# motherboard_zaloha_s_medi.net
KiCad netlist of a schematic drawn in EAGLE
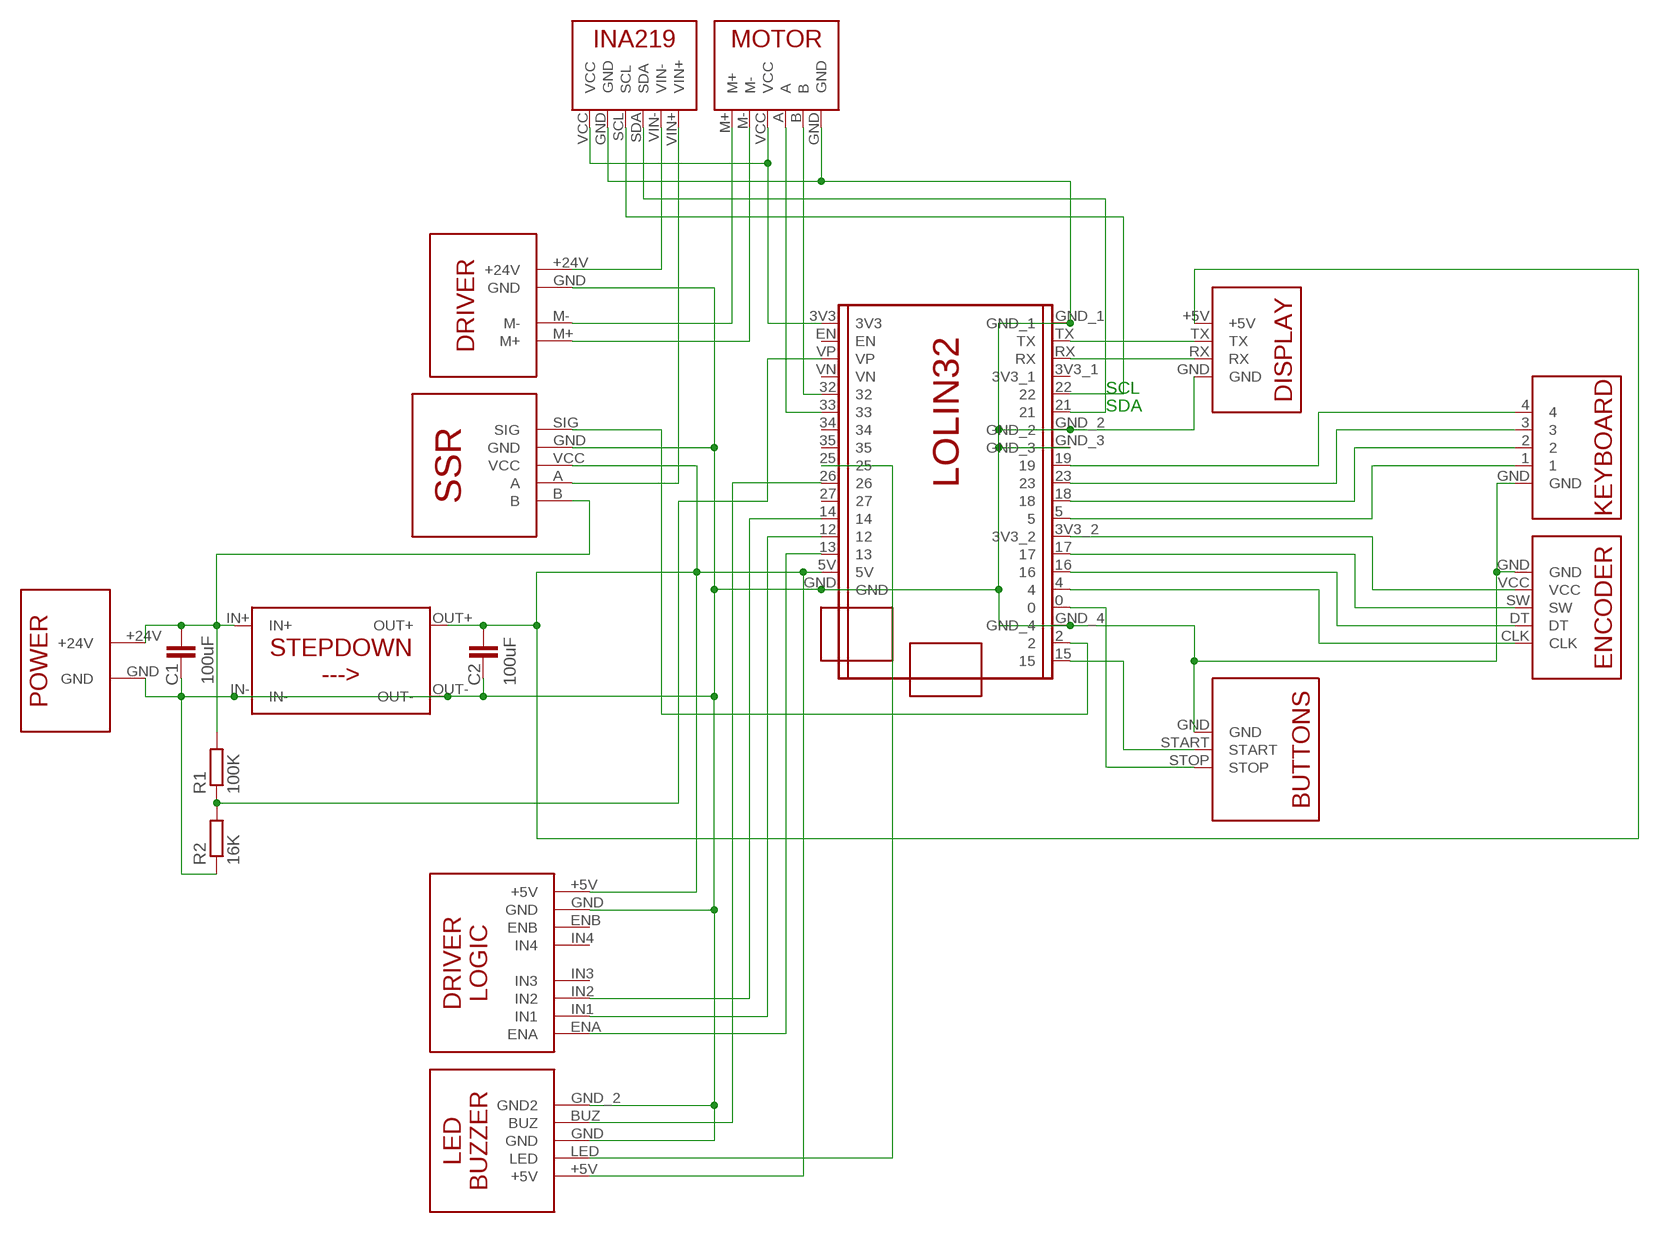
[diagram p0: schematic, sheet 1]

(export (version "E")
  (design (tool "Eeschema 10.0.6"))
  (components
    (comp (ref "C1")
      (value "100uF")
      (footprint "eagle-import:C5B2.5")
      (libsource (lib "eagle-import") (part "C5/2.5"))
    )
    (comp (ref "C2")
      (value "100uF")
      (footprint "eagle-import:C5B2.5")
      (libsource (lib "eagle-import") (part "C5/2.5"))
    )
    (comp (ref "R1")
      (value "100K")
      (footprint "eagle-import:0207_7")
      (libsource (lib "eagle-import") (part "R-EU_0207/7"))
    )
    (comp (ref "R2")
      (value "16K")
      (footprint "eagle-import:0207_7")
      (libsource (lib "eagle-import") (part "R-EU_0207/7"))
    )
    (comp (ref "U$1")
      (value "B_DISPLAY")
      (footprint "eagle-import:B_DISPLAY")
      (libsource (lib "eagle-import") (part "B_DISPLAY"))
    )
    (comp (ref "U$2")
      (value "INA219")
      (footprint "eagle-import:INA219")
      (libsource (lib "eagle-import") (part "INA219"))
    )
    (comp (ref "U$3")
      (value "B_MOTOR")
      (footprint "eagle-import:B_MOTOR")
      (libsource (lib "eagle-import") (part "B_MOTOR"))
    )
    (comp (ref "U$4")
      (value "B_KLAVESNICE")
      (footprint "eagle-import:B_KLAVESNICE")
      (libsource (lib "eagle-import") (part "B_KLAVESNICE"))
    )
    (comp (ref "U$5")
      (value "B_LED_BUZ")
      (footprint "eagle-import:B_LED_BUZ")
      (libsource (lib "eagle-import") (part "B_LED_BUZ"))
    )
    (comp (ref "U$6")
      (value "B_ENCODER")
      (footprint "eagle-import:B_ENCODER")
      (libsource (lib "eagle-import") (part "B_ENCODER"))
    )
    (comp (ref "U$7")
      (value "B_SSR_2")
      (footprint "eagle-import:B_SSR_2")
      (libsource (lib "eagle-import") (part "B_SSR_2"))
    )
    (comp (ref "U$8")
      (value "B_LOLIN32")
      (footprint "eagle-import:B_LOLIN32")
      (libsource (lib "eagle-import") (part "B_LOLIN32"))
    )
    (comp (ref "U$9")
      (value "B_STEPDOWN")
      (footprint "eagle-import:B_STEPDOWN")
      (libsource (lib "eagle-import") (part "B_STEPDOWN"))
    )
    (comp (ref "U$10")
      (value "B_DRIVER_3")
      (footprint "eagle-import:B_DRIVER_3")
      (libsource (lib "eagle-import") (part "B_DRIVER_3"))
    )
    (comp (ref "U$11")
      (value "B_POWER")
      (footprint "eagle-import:B_POWER")
      (libsource (lib "eagle-import") (part "B_POWER"))
    )
    (comp (ref "U$12")
      (value "B_DRIVER_2")
      (footprint "eagle-import:B_DRIVER_2")
      (libsource (lib "eagle-import") (part "B_DRIVER_2"))
    )
    (comp (ref "U$13")
      (value "B_BUTTONS")
      (footprint "eagle-import:B_BUTTONS")
      (libsource (lib "eagle-import") (part "B_BUTTONS"))
    )
  )
  (nets
    (net (code "1") (name "Net-(C1-Pad1)") (class "Default")
      (node (ref "C1") (pin "1") (pinfunction "1_1") (pintype "passive"))
      (node (ref "R1") (pin "2") (pinfunction "2_2") (pintype "passive"))
      (node (ref "U$11") (pin "+24V") (pinfunction "+24V_+24V") (pintype "bidirectional"))
      (node (ref "U$7") (pin "B") (pinfunction "B_B") (pintype "bidirectional"))
      (node (ref "U$9") (pin "IN+") (pinfunction "IN+_IN+") (pintype "bidirectional"))
    )
    (net (code "2") (name "Net-(C2-Pad1)") (class "Default")
      (node (ref "C2") (pin "1") (pinfunction "1_1") (pintype "passive"))
      (node (ref "U$1") (pin "+5V") (pinfunction "+5V_+5V") (pintype "bidirectional"))
      (node (ref "U$10") (pin "+5V") (pinfunction "+5V_+5V") (pintype "bidirectional"))
      (node (ref "U$5") (pin "+5V") (pinfunction "+5V_+5V") (pintype "bidirectional"))
      (node (ref "U$7") (pin "VCC") (pinfunction "VCC_VCC") (pintype "bidirectional"))
      (node (ref "U$8") (pin "5V") (pinfunction "5V_5V") (pintype "bidirectional"))
      (node (ref "U$9") (pin "OUT+") (pinfunction "OUT+_OUT+") (pintype "bidirectional"))
    )
    (net (code "3") (name "Net-(R1-Pad1)") (class "Default")
      (node (ref "R1") (pin "1") (pinfunction "1_1") (pintype "passive"))
      (node (ref "R2") (pin "2") (pinfunction "2_2") (pintype "passive"))
      (node (ref "U$8") (pin "VP") (pinfunction "VP_VP") (pintype "bidirectional"))
    )
    (net (code "4") (name "Net-(U$1-PadRX)") (class "Default")
      (node (ref "U$1") (pin "RX") (pinfunction "RX_RX") (pintype "bidirectional"))
      (node (ref "U$8") (pin "RX") (pinfunction "RX_RX") (pintype "bidirectional"))
    )
    (net (code "5") (name "Net-(U$1-PadTX)") (class "Default")
      (node (ref "U$1") (pin "TX") (pinfunction "TX_TX") (pintype "bidirectional"))
      (node (ref "U$8") (pin "TX") (pinfunction "TX_TX") (pintype "bidirectional"))
    )
    (net (code "6") (name "Net-(U$2-PadSCL)") (class "Default")
      (node (ref "U$2") (pin "SCL") (pinfunction "SCL_SCL") (pintype "bidirectional"))
      (node (ref "U$8") (pin "22") (pinfunction "22_22") (pintype "bidirectional"))
    )
    (net (code "7") (name "Net-(U$2-PadSDA)") (class "Default")
      (node (ref "U$2") (pin "SDA") (pinfunction "SDA_SDA") (pintype "bidirectional"))
      (node (ref "U$8") (pin "21") (pinfunction "21_21") (pintype "bidirectional"))
    )
    (net (code "8") (name "Net-(U$2-PadVCC)") (class "Default")
      (node (ref "U$2") (pin "VCC") (pinfunction "VCC_VCC") (pintype "bidirectional"))
      (node (ref "U$3") (pin "VCC") (pinfunction "VCC_VCC") (pintype "bidirectional"))
      (node (ref "U$8") (pin "3V3") (pinfunction "3V3_3V3") (pintype "bidirectional"))
    )
    (net (code "9") (name "Net-(U$2-PadVIN+)") (class "Default")
      (node (ref "U$2") (pin "VIN+") (pinfunction "VIN+_VIN+") (pintype "bidirectional"))
      (node (ref "U$7") (pin "A") (pinfunction "A_A") (pintype "bidirectional"))
    )
    (net (code "10") (name "Net-(U$3-PadA)") (class "Default")
      (node (ref "U$3") (pin "A") (pinfunction "A_A") (pintype "bidirectional"))
      (node (ref "U$8") (pin "33") (pinfunction "33_33") (pintype "bidirectional"))
    )
    (net (code "11") (name "Net-(U$3-PadB)") (class "Default")
      (node (ref "U$3") (pin "B") (pinfunction "B_B") (pintype "bidirectional"))
      (node (ref "U$8") (pin "32") (pinfunction "32_32") (pintype "bidirectional"))
    )
    (net (code "12") (name "Net-(U$4-Pad1)") (class "Default")
      (node (ref "U$4") (pin "1") (pinfunction "1_1") (pintype "bidirectional"))
      (node (ref "U$8") (pin "5") (pinfunction "5_5") (pintype "bidirectional"))
    )
    (net (code "13") (name "Net-(U$4-Pad2)") (class "Default")
      (node (ref "U$4") (pin "2") (pinfunction "2_2") (pintype "bidirectional"))
      (node (ref "U$8") (pin "18") (pinfunction "18_18") (pintype "bidirectional"))
    )
    (net (code "14") (name "Net-(U$4-Pad3)") (class "Default")
      (node (ref "U$4") (pin "3") (pinfunction "3_3") (pintype "bidirectional"))
      (node (ref "U$8") (pin "23") (pinfunction "23_23") (pintype "bidirectional"))
    )
    (net (code "15") (name "Net-(U$4-Pad4)") (class "Default")
      (node (ref "U$4") (pin "4") (pinfunction "4_4") (pintype "bidirectional"))
      (node (ref "U$8") (pin "19") (pinfunction "19_19") (pintype "bidirectional"))
    )
    (net (code "16") (name "Net-(U$5-GND2)") (class "Default")
      (node (ref "C1") (pin "2") (pinfunction "2_2") (pintype "passive"))
      (node (ref "C2") (pin "2") (pinfunction "2_2") (pintype "passive"))
      (node (ref "R2") (pin "1") (pinfunction "1_1") (pintype "passive"))
      (node (ref "U$1") (pin "GND") (pinfunction "GND_GND") (pintype "bidirectional"))
      (node (ref "U$10") (pin "GND") (pinfunction "GND_GND") (pintype "bidirectional"))
      (node (ref "U$11") (pin "GND") (pinfunction "GND_GND") (pintype "bidirectional"))
      (node (ref "U$12") (pin "GND") (pinfunction "GND_GND") (pintype "bidirectional"))
      (node (ref "U$13") (pin "GND") (pinfunction "GND_GND") (pintype "bidirectional"))
      (node (ref "U$2") (pin "GND") (pinfunction "GND_GND") (pintype "bidirectional"))
      (node (ref "U$3") (pin "GND") (pinfunction "GND_GND") (pintype "bidirectional"))
      (node (ref "U$4") (pin "GND") (pinfunction "GND_GND") (pintype "bidirectional"))
      (node (ref "U$5") (pin "GND") (pinfunction "GND_GND") (pintype "bidirectional"))
      (node (ref "U$5") (pin "GND_2") (pinfunction "GND2_GND_2") (pintype "bidirectional"))
      (node (ref "U$6") (pin "GND") (pinfunction "GND_GND") (pintype "bidirectional"))
      (node (ref "U$7") (pin "GND") (pinfunction "GND_GND") (pintype "bidirectional"))
      (node (ref "U$8") (pin "GND") (pinfunction "GND_GND") (pintype "bidirectional"))
      (node (ref "U$8") (pin "GND_1") (pinfunction "GND_1_GND_1") (pintype "bidirectional"))
      (node (ref "U$8") (pin "GND_2") (pinfunction "GND_2_GND_2") (pintype "bidirectional"))
      (node (ref "U$8") (pin "GND_3") (pinfunction "GND_3_GND_3") (pintype "bidirectional"))
      (node (ref "U$8") (pin "GND_4") (pinfunction "GND_4_GND_4") (pintype "bidirectional"))
      (node (ref "U$9") (pin "IN-") (pinfunction "IN-_IN-") (pintype "bidirectional"))
      (node (ref "U$9") (pin "OUT-") (pinfunction "OUT-_OUT-") (pintype "bidirectional"))
    )
    (net (code "17") (name "Net-(U$5-PadBUZ)") (class "Default")
      (node (ref "U$5") (pin "BUZ") (pinfunction "BUZ_BUZ") (pintype "bidirectional"))
      (node (ref "U$8") (pin "26") (pinfunction "26_26") (pintype "bidirectional"))
    )
    (net (code "18") (name "Net-(U$5-PadLED)") (class "Default")
      (node (ref "U$5") (pin "LED") (pinfunction "LED_LED") (pintype "bidirectional"))
      (node (ref "U$8") (pin "25") (pinfunction "25_25") (pintype "bidirectional"))
    )
    (net (code "19") (name "Net-(U$6-PadCLK)") (class "Default")
      (node (ref "U$6") (pin "CLK") (pinfunction "CLK_CLK") (pintype "bidirectional"))
      (node (ref "U$8") (pin "4") (pinfunction "4_4") (pintype "bidirectional"))
    )
    (net (code "20") (name "Net-(U$6-PadDT)") (class "Default")
      (node (ref "U$6") (pin "DT") (pinfunction "DT_DT") (pintype "bidirectional"))
      (node (ref "U$8") (pin "16") (pinfunction "16_16") (pintype "bidirectional"))
    )
    (net (code "21") (name "Net-(U$6-PadSW)") (class "Default")
      (node (ref "U$6") (pin "SW") (pinfunction "SW_SW") (pintype "bidirectional"))
      (node (ref "U$8") (pin "17") (pinfunction "17_17") (pintype "bidirectional"))
    )
    (net (code "22") (name "Net-(U$6-PadVCC)") (class "Default")
      (node (ref "U$6") (pin "VCC") (pinfunction "VCC_VCC") (pintype "bidirectional"))
      (node (ref "U$8") (pin "3V3_2") (pinfunction "3V3_2_3V3_2") (pintype "bidirectional"))
    )
    (net (code "23") (name "Net-(U$7-PadSIG)") (class "Default")
      (node (ref "U$7") (pin "SIG") (pinfunction "SIG_SIG") (pintype "bidirectional"))
      (node (ref "U$8") (pin "2") (pinfunction "2_2") (pintype "bidirectional"))
    )
    (net (code "24") (name "Net-(U$10-PadENA)") (class "Default")
      (node (ref "U$10") (pin "ENA") (pinfunction "ENA_ENA") (pintype "bidirectional"))
      (node (ref "U$8") (pin "13") (pinfunction "13_13") (pintype "bidirectional"))
    )
    (net (code "25") (name "Net-(U$10-PadIN1)") (class "Default")
      (node (ref "U$10") (pin "IN1") (pinfunction "IN1_IN1") (pintype "bidirectional"))
      (node (ref "U$8") (pin "12") (pinfunction "12_12") (pintype "bidirectional"))
    )
    (net (code "26") (name "Net-(U$10-PadIN2)") (class "Default")
      (node (ref "U$10") (pin "IN2") (pinfunction "IN2_IN2") (pintype "bidirectional"))
      (node (ref "U$8") (pin "14") (pinfunction "14_14") (pintype "bidirectional"))
    )
    (net (code "27") (name "Net-(U$12-Pad+24V)") (class "Default")
      (node (ref "U$12") (pin "+24V") (pinfunction "+24V_+24V") (pintype "bidirectional"))
      (node (ref "U$2") (pin "VIN-") (pinfunction "VIN-_VIN-") (pintype "bidirectional"))
    )
    (net (code "28") (name "Net-(U$12-PadM+)") (class "Default")
      (node (ref "U$12") (pin "M+") (pinfunction "M+_M+") (pintype "bidirectional"))
      (node (ref "U$3") (pin "M-") (pinfunction "M-_M-") (pintype "bidirectional"))
    )
    (net (code "29") (name "Net-(U$12-PadM-)") (class "Default")
      (node (ref "U$12") (pin "M-") (pinfunction "M-_M-") (pintype "bidirectional"))
      (node (ref "U$3") (pin "M+") (pinfunction "M+_M+") (pintype "bidirectional"))
    )
    (net (code "30") (name "Net-(U$13-PadSTART)") (class "Default")
      (node (ref "U$13") (pin "START") (pinfunction "START_START") (pintype "bidirectional"))
      (node (ref "U$8") (pin "15") (pinfunction "15_15") (pintype "bidirectional"))
    )
    (net (code "31") (name "Net-(U$13-PadSTOP)") (class "Default")
      (node (ref "U$13") (pin "STOP") (pinfunction "STOP_STOP") (pintype "bidirectional"))
      (node (ref "U$8") (pin "0") (pinfunction "0_0") (pintype "bidirectional"))
    )
    (net (code "32") (name "unconnected-(U$8-Pad3V3_1)") (class "Default")
      (node (ref "U$8") (pin "3V3_1") (pinfunction "3V3_1_3V3_1") (pintype "bidirectional"))
    )
    (net (code "33") (name "unconnected-(U$8-Pad27)") (class "Default")
      (node (ref "U$8") (pin "27") (pinfunction "27_27") (pintype "bidirectional"))
    )
    (net (code "34") (name "unconnected-(U$8-Pad34)") (class "Default")
      (node (ref "U$8") (pin "34") (pinfunction "34_34") (pintype "bidirectional"))
    )
    (net (code "35") (name "unconnected-(U$8-Pad35)") (class "Default")
      (node (ref "U$8") (pin "35") (pinfunction "35_35") (pintype "bidirectional"))
    )
    (net (code "36") (name "unconnected-(U$8-PadEN)") (class "Default")
      (node (ref "U$8") (pin "EN") (pinfunction "EN_EN") (pintype "bidirectional"))
    )
    (net (code "37") (name "unconnected-(U$8-PadVN)") (class "Default")
      (node (ref "U$8") (pin "VN") (pinfunction "VN_VN") (pintype "bidirectional"))
    )
    (net (code "38") (name "unconnected-(U$10-PadENB)") (class "Default")
      (node (ref "U$10") (pin "ENB") (pinfunction "ENB_ENB") (pintype "bidirectional"))
    )
    (net (code "39") (name "unconnected-(U$10-PadIN3)") (class "Default")
      (node (ref "U$10") (pin "IN3") (pinfunction "IN3_IN3") (pintype "bidirectional"))
    )
    (net (code "40") (name "unconnected-(U$10-PadIN4)") (class "Default")
      (node (ref "U$10") (pin "IN4") (pinfunction "IN4_IN4") (pintype "bidirectional"))
    )
  )
)
